# Lcd16x2_Backpack.net
KiCad netlist of a schematic drawn in EAGLE
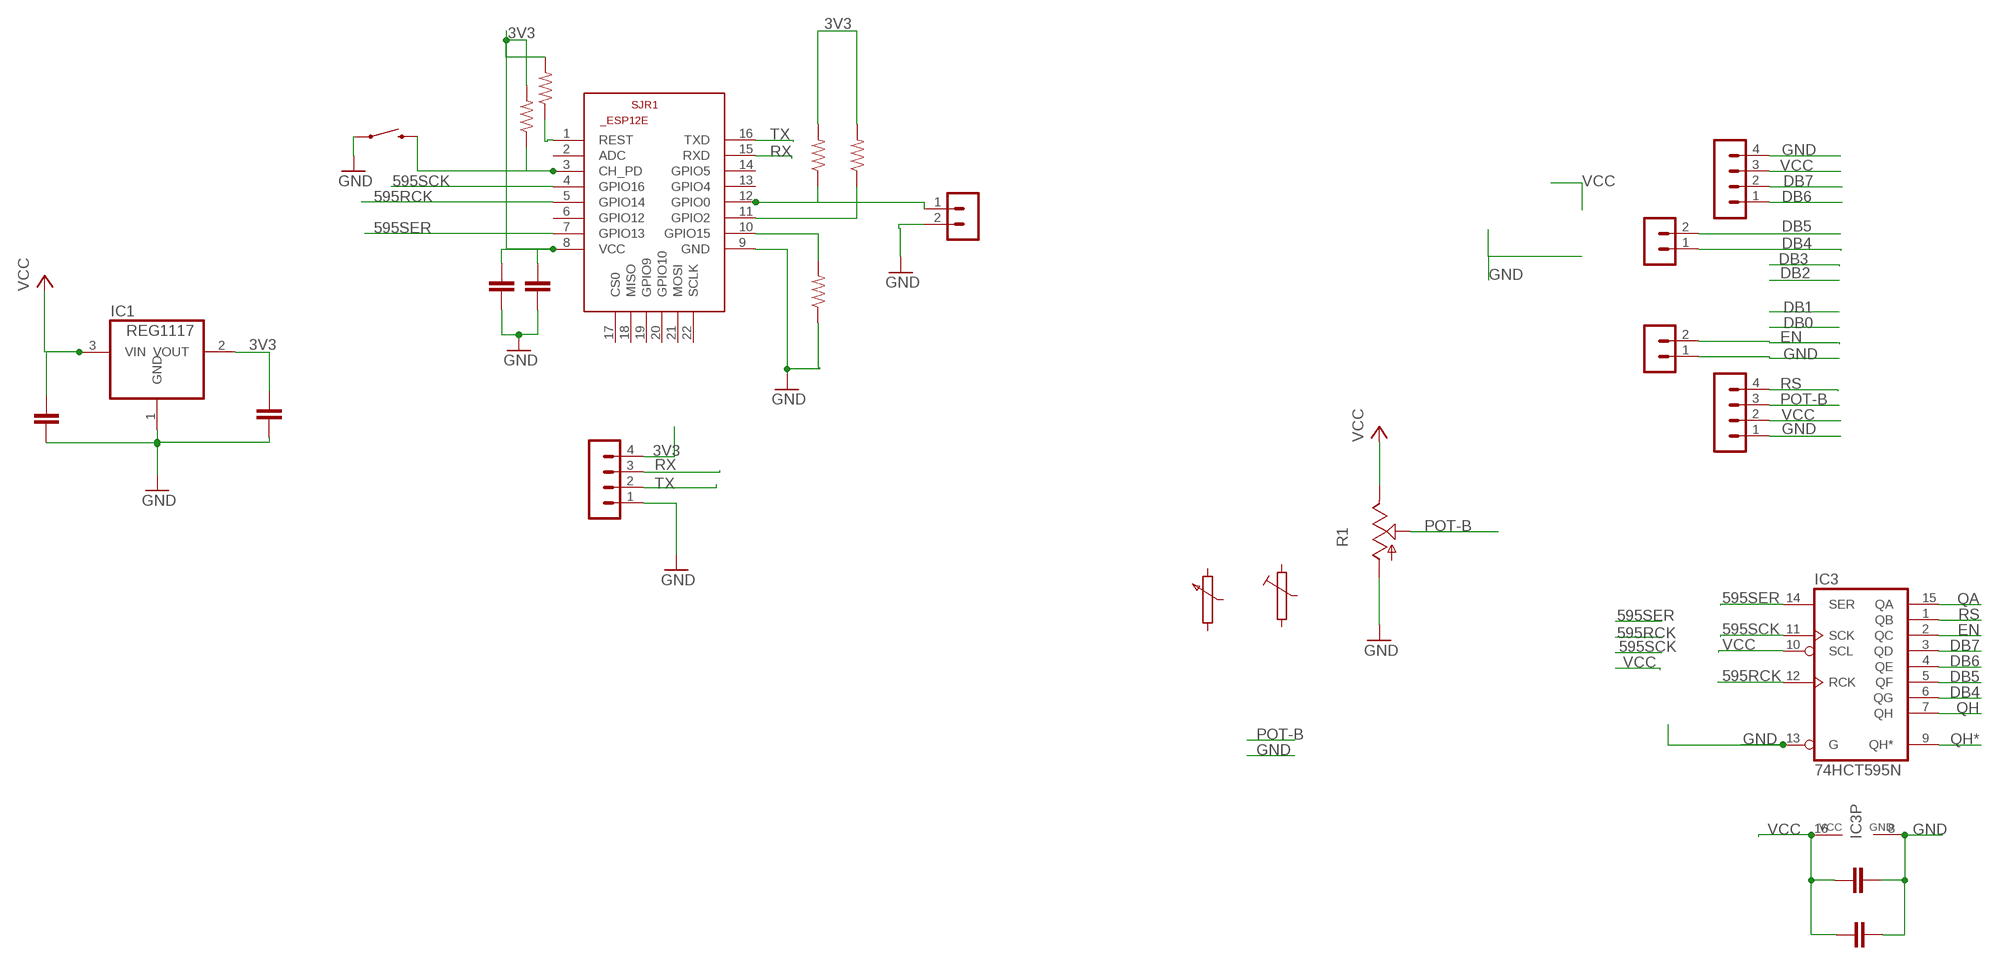
[diagram p0: schematic, sheet 1]

(export (version "E")
  (design (tool "Eeschema 10.0.6"))
  (components
    (comp (ref "IC1")
      (value "REG1117")
      (footprint "eagle-import:SOT223")
      (libsource (lib "eagle-import") (part "REG1117"))
    )
    (comp (ref "IC3")
      (value "74HCT595N")
      (footprint "eagle-import:DIL16")
      (libsource (lib "eagle-import") (part "74595NHCT"))
    )
    (comp (ref "R1")
      (value "TRIM_US-RJ9W")
      (footprint "eagle-import:RJ9W")
      (libsource (lib "eagle-import") (part "TRIM_US-RJ9W"))
    )
    (comp (ref "SJR1")
      (value "ESP8266-12EESP12E")
      (footprint "eagle-import:ESP8266-ESP12E")
      (libsource (lib "eagle-import") (part "ESP8266-12EESP12E"))
    )
    (comp (ref "U$1")
      (value "RESISTOR-0.41206")
      (footprint "eagle-import:1206")
      (libsource (lib "eagle-import") (part "RESISTOR-0.41206"))
    )
    (comp (ref "U$2")
      (value "HEADER-4PIN")
      (footprint "eagle-import:HEADER-4PIN")
      (libsource (lib "eagle-import") (part "HEADER-4PIN"))
    )
    (comp (ref "U$5")
      (value "RESISTOR-0.41206")
      (footprint "eagle-import:1206")
      (libsource (lib "eagle-import") (part "RESISTOR-0.41206"))
    )
    (comp (ref "U$6")
      (value "RESISTOR-0.41206")
      (footprint "eagle-import:1206")
      (libsource (lib "eagle-import") (part "RESISTOR-0.41206"))
    )
    (comp (ref "U$7")
      (value "RESISTOR-0.41206")
      (footprint "eagle-import:1206")
      (libsource (lib "eagle-import") (part "RESISTOR-0.41206"))
    )
    (comp (ref "U$8")
      (value "RESISTOR-0.41206")
      (footprint "eagle-import:1206")
      (libsource (lib "eagle-import") (part "RESISTOR-0.41206"))
    )
    (comp (ref "U$9")
      (value "HEADER-4PIN")
      (footprint "eagle-import:HEADER-4PIN")
      (libsource (lib "eagle-import") (part "HEADER-4PIN"))
    )
    (comp (ref "U$10")
      (value "SWITCH-MOMENTARY")
      (footprint "eagle-import:TACTILE-6X6")
      (libsource (lib "eagle-import") (part "SWITCH-MOMENTARY"))
    )
    (comp (ref "U$11")
      (value "HEADER-2PINA")
      (footprint "eagle-import:HEADER-2PIN")
      (libsource (lib "eagle-import") (part "HEADER-2PINA"))
    )
    (comp (ref "U$12")
      (value "CAPACITOR-0.2-CER1206")
      (footprint "eagle-import:1206")
      (libsource (lib "eagle-import") (part "CAPACITOR-0.2-CER1206"))
    )
    (comp (ref "U$13")
      (value "CAPACITOR-0.2-CER1206")
      (footprint "eagle-import:1206")
      (libsource (lib "eagle-import") (part "CAPACITOR-0.2-CER1206"))
    )
    (comp (ref "U$14")
      (value "HEADER-2PINA")
      (footprint "eagle-import:HEADER-2PIN")
      (libsource (lib "eagle-import") (part "HEADER-2PINA"))
    )
    (comp (ref "U$15")
      (value "HEADER-4PIN")
      (footprint "eagle-import:HEADER-4PIN")
      (libsource (lib "eagle-import") (part "HEADER-4PIN"))
    )
    (comp (ref "U$16")
      (value "CAPACITOR-0.2-CER1206")
      (footprint "eagle-import:1206")
      (libsource (lib "eagle-import") (part "CAPACITOR-0.2-CER1206"))
    )
    (comp (ref "U$17")
      (value "CAPACITOR-0.2-CER1206")
      (footprint "eagle-import:1206")
      (libsource (lib "eagle-import") (part "CAPACITOR-0.2-CER1206"))
    )
    (comp (ref "U$21")
      (value "CAPACITOR-0.2-CER1206")
      (footprint "eagle-import:1206")
      (libsource (lib "eagle-import") (part "CAPACITOR-0.2-CER1206"))
    )
    (comp (ref "U$22")
      (value "CAPACITOR-0.2-CER1206")
      (footprint "eagle-import:1206")
      (libsource (lib "eagle-import") (part "CAPACITOR-0.2-CER1206"))
    )
    (comp (ref "U$23")
      (value "HEADER-2PINA")
      (footprint "eagle-import:HEADER-2PIN")
      (libsource (lib "eagle-import") (part "HEADER-2PINA"))
    )
  )
  (nets
    (net (code "1") (name "/3V3") (class "Default")
      (node (ref "IC1") (pin "2") (pinfunction "VOUT_2") (pintype "output"))
      (node (ref "SJR1") (pin "8") (pinfunction "VCC_8") (pintype "bidirectional"))
      (node (ref "U$13") (pin "2") (pinfunction "2_2") (pintype "passive"))
      (node (ref "U$16") (pin "2") (pinfunction "2_2") (pintype "passive"))
      (node (ref "U$17") (pin "2") (pinfunction "2_2") (pintype "passive"))
      (node (ref "U$5") (pin "2") (pinfunction "2_2") (pintype "passive"))
      (node (ref "U$6") (pin "2") (pinfunction "2_2") (pintype "passive"))
      (node (ref "U$7") (pin "2") (pinfunction "2_2") (pintype "passive"))
      (node (ref "U$8") (pin "2") (pinfunction "2_2") (pintype "passive"))
      (node (ref "U$9") (pin "4") (pinfunction "4_4") (pintype "passive"))
    )
    (net (code "2") (name "/595RCK") (class "Default")
      (node (ref "IC3") (pin "12") (pinfunction "RCK_12") (pintype "input"))
      (node (ref "SJR1") (pin "5") (pinfunction "GPIO14_5") (pintype "bidirectional"))
    )
    (net (code "3") (name "/595SCK") (class "Default")
      (node (ref "IC3") (pin "11") (pinfunction "SCK_11") (pintype "input"))
      (node (ref "SJR1") (pin "4") (pinfunction "GPIO16_4") (pintype "bidirectional"))
    )
    (net (code "4") (name "/595SER") (class "Default")
      (node (ref "IC3") (pin "14") (pinfunction "SER_14") (pintype "input"))
      (node (ref "SJR1") (pin "7") (pinfunction "GPIO13_7") (pintype "bidirectional"))
    )
    (net (code "9") (name "/DB4") (class "Default")
      (node (ref "IC3") (pin "6") (pinfunction "QG_6") (pintype "tri_state"))
      (node (ref "U$14") (pin "1") (pinfunction "2_1") (pintype "passive"))
    )
    (net (code "10") (name "/DB5") (class "Default")
      (node (ref "IC3") (pin "5") (pinfunction "QF_5") (pintype "tri_state"))
      (node (ref "U$14") (pin "2") (pinfunction "3_2") (pintype "passive"))
    )
    (net (code "11") (name "/DB6") (class "Default")
      (node (ref "IC3") (pin "4") (pinfunction "QE_4") (pintype "tri_state"))
      (node (ref "U$2") (pin "1") (pinfunction "1_1") (pintype "passive"))
    )
    (net (code "12") (name "/DB7") (class "Default")
      (node (ref "IC3") (pin "3") (pinfunction "QD_3") (pintype "tri_state"))
      (node (ref "U$2") (pin "2") (pinfunction "2_2") (pintype "passive"))
    )
    (net (code "13") (name "/EN") (class "Default")
      (node (ref "IC3") (pin "2") (pinfunction "QC_2") (pintype "tri_state"))
      (node (ref "U$23") (pin "2") (pinfunction "3_2") (pintype "passive"))
    )
    (net (code "14") (name "/POT-B") (class "Default")
      (node (ref "R1") (pin "S") (pinfunction "S_S") (pintype "passive"))
      (node (ref "U$15") (pin "3") (pinfunction "3_3") (pintype "passive"))
    )
    (net (code "15") (name "/QA") (class "Default")
      (node (ref "IC3") (pin "15") (pinfunction "QA_15") (pintype "tri_state"))
    )
    (net (code "16") (name "/QH") (class "Default")
      (node (ref "IC3") (pin "7") (pinfunction "QH_7") (pintype "tri_state"))
    )
    (net (code "17") (name "/QH*") (class "Default")
      (node (ref "IC3") (pin "9") (pinfunction "QH*_9") (pintype "tri_state"))
    )
    (net (code "18") (name "/RS") (class "Default")
      (node (ref "IC3") (pin "1") (pinfunction "QB_1") (pintype "tri_state"))
      (node (ref "U$15") (pin "4") (pinfunction "4_4") (pintype "passive"))
    )
    (net (code "19") (name "/RX") (class "Default")
      (node (ref "SJR1") (pin "15") (pinfunction "RXD_15") (pintype "bidirectional"))
      (node (ref "U$9") (pin "3") (pinfunction "3_3") (pintype "passive"))
    )
    (net (code "20") (name "/TX") (class "Default")
      (node (ref "SJR1") (pin "16") (pinfunction "TXD_16") (pintype "bidirectional"))
      (node (ref "U$9") (pin "2") (pinfunction "2_2") (pintype "passive"))
    )
    (net (code "21") (name "GND") (class "Default")
      (node (ref "IC1") (pin "1") (pinfunction "GND_1") (pintype "power_in"))
      (node (ref "IC3") (pin "13") (pinfunction "G_13") (pintype "input"))
      (node (ref "IC3") (pin "8") (pinfunction "GND_8") (pintype "power_in"))
      (node (ref "R1") (pin "A") (pinfunction "A_A") (pintype "passive"))
      (node (ref "SJR1") (pin "9") (pinfunction "GND_9") (pintype "bidirectional"))
      (node (ref "U$1") (pin "1") (pinfunction "1_1") (pintype "passive"))
      (node (ref "U$10") (pin "1") (pinfunction "1_1") (pintype "passive"))
      (node (ref "U$10") (pin "2") (pinfunction "1_2") (pintype "passive"))
      (node (ref "U$11") (pin "2") (pinfunction "3_2") (pintype "passive"))
      (node (ref "U$12") (pin "1") (pinfunction "1_1") (pintype "passive"))
      (node (ref "U$13") (pin "1") (pinfunction "1_1") (pintype "passive"))
      (node (ref "U$15") (pin "1") (pinfunction "1_1") (pintype "passive"))
      (node (ref "U$16") (pin "1") (pinfunction "1_1") (pintype "passive"))
      (node (ref "U$17") (pin "1") (pinfunction "1_1") (pintype "passive"))
      (node (ref "U$2") (pin "4") (pinfunction "4_4") (pintype "passive"))
      (node (ref "U$21") (pin "2") (pinfunction "2_2") (pintype "passive"))
      (node (ref "U$22") (pin "2") (pinfunction "2_2") (pintype "passive"))
      (node (ref "U$23") (pin "1") (pinfunction "2_1") (pintype "passive"))
      (node (ref "U$9") (pin "1") (pinfunction "1_1") (pintype "passive"))
    )
    (net (code "22") (name "Net-(SJR1-CH_PD)") (class "Default")
      (node (ref "SJR1") (pin "3") (pinfunction "CH_PD_3") (pintype "bidirectional"))
      (node (ref "U$10") (pin "3") (pinfunction "2_3") (pintype "passive"))
      (node (ref "U$10") (pin "4") (pinfunction "2_4") (pintype "passive"))
      (node (ref "U$7") (pin "1") (pinfunction "1_1") (pintype "passive"))
    )
    (net (code "23") (name "Net-(SJR1-GPIO0)") (class "Default")
      (node (ref "SJR1") (pin "12") (pinfunction "GPIO0_12") (pintype "bidirectional"))
      (node (ref "U$11") (pin "1") (pinfunction "2_1") (pintype "passive"))
      (node (ref "U$5") (pin "1") (pinfunction "1_1") (pintype "passive"))
    )
    (net (code "24") (name "Net-(SJR1-GPIO2)") (class "Default")
      (node (ref "SJR1") (pin "11") (pinfunction "GPIO2_11") (pintype "bidirectional"))
      (node (ref "U$6") (pin "1") (pinfunction "1_1") (pintype "passive"))
    )
    (net (code "25") (name "Net-(SJR1-GPIO15)") (class "Default")
      (node (ref "SJR1") (pin "10") (pinfunction "GPIO15_10") (pintype "bidirectional"))
      (node (ref "U$1") (pin "2") (pinfunction "2_2") (pintype "passive"))
    )
    (net (code "26") (name "Net-(SJR1-REST)") (class "Default")
      (node (ref "SJR1") (pin "1") (pinfunction "REST_1") (pintype "bidirectional"))
      (node (ref "U$8") (pin "1") (pinfunction "1_1") (pintype "passive"))
    )
    (net (code "27") (name "VCC") (class "Default")
      (node (ref "IC1") (pin "3") (pinfunction "VIN_3") (pintype "input"))
      (node (ref "IC3") (pin "10") (pinfunction "SCL_10") (pintype "input"))
      (node (ref "IC3") (pin "16") (pinfunction "VCC_16") (pintype "power_in"))
      (node (ref "R1") (pin "E") (pinfunction "E_E") (pintype "passive"))
      (node (ref "U$12") (pin "2") (pinfunction "2_2") (pintype "passive"))
      (node (ref "U$15") (pin "2") (pinfunction "2_2") (pintype "passive"))
      (node (ref "U$2") (pin "3") (pinfunction "3_3") (pintype "passive"))
      (node (ref "U$21") (pin "1") (pinfunction "1_1") (pintype "passive"))
      (node (ref "U$22") (pin "1") (pinfunction "1_1") (pintype "passive"))
    )
    (net (code "28") (name "unconnected-(SJR1-ADC-Pad2)") (class "Default")
      (node (ref "SJR1") (pin "2") (pinfunction "ADC_2") (pintype "bidirectional"))
    )
    (net (code "29") (name "unconnected-(SJR1-CS0-Pad17)") (class "Default")
      (node (ref "SJR1") (pin "17") (pinfunction "CS0_17") (pintype "bidirectional"))
    )
    (net (code "30") (name "unconnected-(SJR1-GPIO4-Pad13)") (class "Default")
      (node (ref "SJR1") (pin "13") (pinfunction "GPIO4_13") (pintype "bidirectional"))
    )
    (net (code "31") (name "unconnected-(SJR1-GPIO5-Pad14)") (class "Default")
      (node (ref "SJR1") (pin "14") (pinfunction "GPIO5_14") (pintype "bidirectional"))
    )
    (net (code "32") (name "unconnected-(SJR1-GPIO9-Pad19)") (class "Default")
      (node (ref "SJR1") (pin "19") (pinfunction "GPIO9_19") (pintype "bidirectional"))
    )
    (net (code "33") (name "unconnected-(SJR1-GPIO10-Pad20)") (class "Default")
      (node (ref "SJR1") (pin "20") (pinfunction "GPIO10_20") (pintype "bidirectional"))
    )
    (net (code "34") (name "unconnected-(SJR1-GPIO12-Pad6)") (class "Default")
      (node (ref "SJR1") (pin "6") (pinfunction "GPIO12_6") (pintype "bidirectional"))
    )
    (net (code "35") (name "unconnected-(SJR1-MISO-Pad18)") (class "Default")
      (node (ref "SJR1") (pin "18") (pinfunction "MISO_18") (pintype "bidirectional"))
    )
    (net (code "36") (name "unconnected-(SJR1-MOSI-Pad21)") (class "Default")
      (node (ref "SJR1") (pin "21") (pinfunction "MOSI_21") (pintype "bidirectional"))
    )
    (net (code "37") (name "unconnected-(SJR1-SCLK-Pad22)") (class "Default")
      (node (ref "SJR1") (pin "22") (pinfunction "SCLK_22") (pintype "bidirectional"))
    )
  )
)
